# KellyConnections.net
KiCad netlist of a schematic drawn in EAGLE
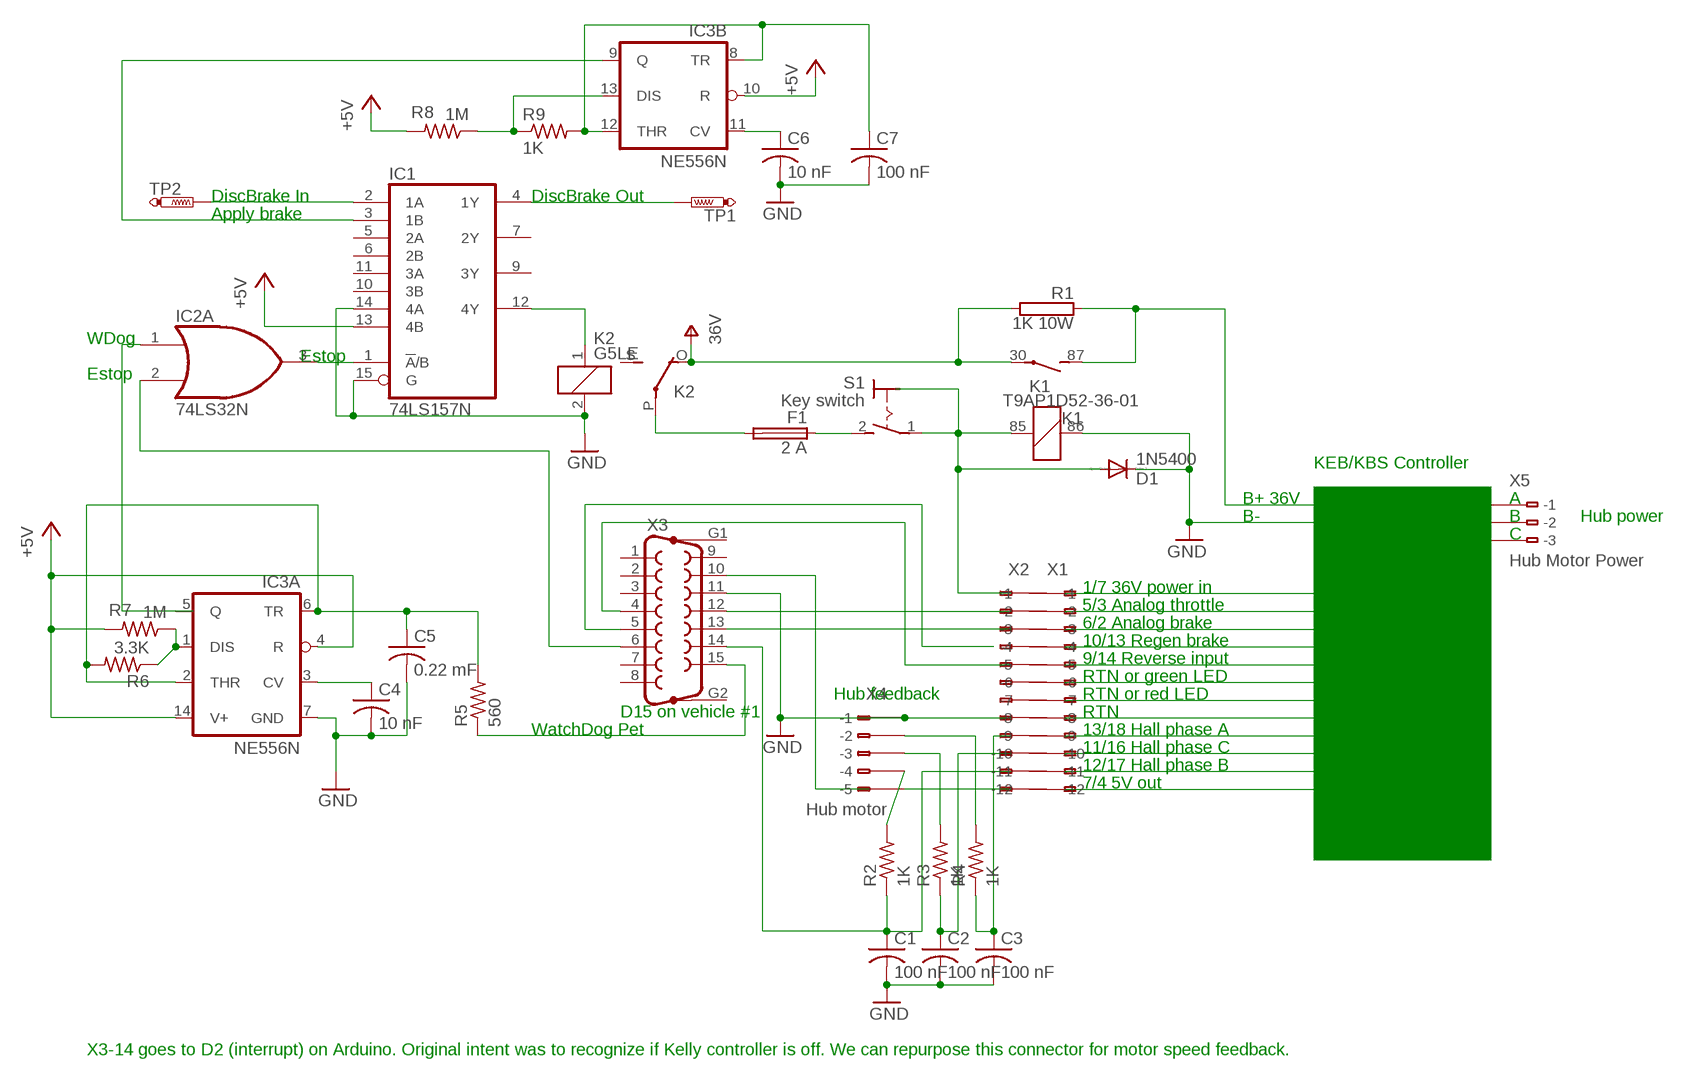
[diagram p0: schematic, sheet 1]

(export (version "E")
  (design (tool "Eeschema 10.0.6"))
  (components
    (comp (ref "C1")
      (value "100 nF")
      (footprint "eagle-import:C025-025X050")
      (libsource (lib "eagle-import") (part "C-US025-025X050"))
    )
    (comp (ref "C2")
      (value "100 nF")
      (footprint "eagle-import:C025-025X050")
      (libsource (lib "eagle-import") (part "C-US025-025X050"))
    )
    (comp (ref "C3")
      (value "100 nF")
      (footprint "eagle-import:C025-025X050")
      (libsource (lib "eagle-import") (part "C-US025-025X050"))
    )
    (comp (ref "C4")
      (value "10 nF")
      (footprint "eagle-import:C025-025X050")
      (libsource (lib "eagle-import") (part "C-US025-025X050"))
    )
    (comp (ref "C5")
      (value "0.22 mF")
      (footprint "eagle-import:C025-025X050")
      (libsource (lib "eagle-import") (part "C-US025-025X050"))
    )
    (comp (ref "C6")
      (value "10 nF")
      (footprint "eagle-import:C025-025X050")
      (libsource (lib "eagle-import") (part "C-US025-025X050"))
    )
    (comp (ref "C7")
      (value "100 nF")
      (footprint "eagle-import:C025-025X050")
      (libsource (lib "eagle-import") (part "C-US025-025X050"))
    )
    (comp (ref "D1")
      (value "1N5400")
      (footprint "eagle-import:DO201-15")
      (libsource (lib "eagle-import") (part "1N5400"))
    )
    (comp (ref "F1")
      (value "2 A")
      (footprint "eagle-import:TE5")
      (libsource (lib "eagle-import") (part "TE5"))
    )
    (comp (ref "IC1")
      (value "74LS157N")
      (footprint "eagle-import:DIL16")
      (libsource (lib "eagle-import") (part "74157NLS"))
    )
    (comp (ref "IC2")
      (value "74LS32N")
      (footprint "eagle-import:DIL14")
      (libsource (lib "eagle-import") (part "7432NLS"))
    )
    (comp (ref "IC3")
      (value "NE556N")
      (footprint "eagle-import:DIL14")
      (libsource (lib "eagle-import") (part "556NNE"))
    )
    (comp (ref "K1")
      (value "T9AP1D52-36-01")
      (footprint "eagle-import:CB1")
      (fields (field (name "MF") "AROMAT/ MATSUSHITA") (field (name "MPN") "CB1A-P-12V"))
      (libsource (lib "eagle-import") (part "CB1A-P-12V"))
    )
    (comp (ref "K2")
      (value "G5LE")
      (footprint "eagle-import:G5LE")
      (libsource (lib "eagle-import") (part "G5LE"))
    )
    (comp (ref "R1")
      (value "1K 10W")
      (footprint "eagle-import:AC07")
      (libsource (lib "eagle-import") (part "RAC07"))
    )
    (comp (ref "R2")
      (value "1K")
      (footprint "eagle-import:0207_15")
      (libsource (lib "eagle-import") (part "R-US_0207/15"))
    )
    (comp (ref "R3")
      (value "1K")
      (footprint "eagle-import:0207_15")
      (libsource (lib "eagle-import") (part "R-US_0207/15"))
    )
    (comp (ref "R4")
      (value "1K")
      (footprint "eagle-import:0207_15")
      (libsource (lib "eagle-import") (part "R-US_0207/15"))
    )
    (comp (ref "R5")
      (value "560")
      (footprint "eagle-import:0207_15")
      (libsource (lib "eagle-import") (part "R-US_0207/15"))
    )
    (comp (ref "R6")
      (value "3.3K")
      (footprint "eagle-import:0207_15")
      (libsource (lib "eagle-import") (part "R-US_0207/15"))
    )
    (comp (ref "R7")
      (value "1M")
      (footprint "eagle-import:0207_15")
      (libsource (lib "eagle-import") (part "R-US_0207/15"))
    )
    (comp (ref "R8")
      (value "1M")
      (footprint "eagle-import:0207_15")
      (libsource (lib "eagle-import") (part "R-US_0207/15"))
    )
    (comp (ref "R9")
      (value "1K")
      (footprint "eagle-import:0207_15")
      (libsource (lib "eagle-import") (part "R-US_0207/15"))
    )
    (comp (ref "S1")
      (value "Key switch")
      (footprint "eagle-import:MS243")
      (libsource (lib "eagle-import") (part "MS243"))
    )
    (comp (ref "TP1")
      (value "PTR1B1,27")
      (footprint "eagle-import:B1,27")
      (libsource (lib "eagle-import") (part "PTR1B1,27"))
    )
    (comp (ref "TP2")
      (value "PTR1B1,27")
      (footprint "eagle-import:B1,27")
      (libsource (lib "eagle-import") (part "PTR1B1,27"))
    )
    (comp (ref "X1")
      (value "233-112")
      (footprint "eagle-import:233-112")
      (libsource (lib "eagle-import") (part "233-112"))
    )
    (comp (ref "X2")
      (value "233-112")
      (footprint "eagle-import:233-112")
      (libsource (lib "eagle-import") (part "233-112"))
    )
    (comp (ref "X3")
      (value "F15HP")
      (footprint "eagle-import:F15HP")
      (libsource (lib "eagle-import") (part "F15HP"))
    )
    (comp (ref "X4")
      (value "Hub motor")
      (footprint "eagle-import:233-105")
      (fields (field (name "MPN") "233-105"))
      (libsource (lib "eagle-import") (part "233-105"))
    )
    (comp (ref "X5")
      (value "Hub Motor Power")
      (footprint "eagle-import:233-103")
      (fields (field (name "MPN") "233-103"))
      (libsource (lib "eagle-import") (part "233-103"))
    )
  )
  (nets
    (net (code "1") (name "+5V") (class "Default")
      (node (ref "IC1") (pin "13") (pinfunction "4B_13") (pintype "input"))
      (node (ref "IC3") (pin "10") (pinfunction "R_10") (pintype "input"))
      (node (ref "IC3") (pin "14") (pinfunction "V+_14") (pintype "power_in"))
      (node (ref "IC3") (pin "4") (pinfunction "R_4") (pintype "input"))
      (node (ref "R7") (pin "2") (pinfunction "2_2") (pintype "passive"))
      (node (ref "R8") (pin "2") (pinfunction "2_2") (pintype "passive"))
    )
    (net (code "2") (name "36V") (class "Default")
      (node (ref "K1") (pin "30") (pinfunction "P_30") (pintype "passive"))
      (node (ref "K2") (pin "O") (pinfunction "O_O") (pintype "passive"))
      (node (ref "R1") (pin "2") (pinfunction "2_2") (pintype "passive"))
    )
    (net (code "3") (name "GND") (class "Default")
      (node (ref "C1") (pin "2") (pinfunction "2_2") (pintype "passive"))
      (node (ref "C2") (pin "2") (pinfunction "2_2") (pintype "passive"))
      (node (ref "C3") (pin "2") (pinfunction "2_2") (pintype "passive"))
      (node (ref "C4") (pin "2") (pinfunction "2_2") (pintype "passive"))
      (node (ref "C5") (pin "2") (pinfunction "2_2") (pintype "passive"))
      (node (ref "C6") (pin "2") (pinfunction "2_2") (pintype "passive"))
      (node (ref "C7") (pin "2") (pinfunction "2_2") (pintype "passive"))
      (node (ref "D1") (pin "C") (pinfunction "C_C") (pintype "passive"))
      (node (ref "IC1") (pin "14") (pinfunction "4A_14") (pintype "input"))
      (node (ref "IC1") (pin "15") (pinfunction "G_15") (pintype "input"))
      (node (ref "IC3") (pin "7") (pinfunction "GND_7") (pintype "power_in"))
      (node (ref "K1") (pin "86") (pinfunction "1_86") (pintype "passive"))
      (node (ref "K2") (pin "2") (pinfunction "2_2") (pintype "passive"))
      (node (ref "X3") (pin "11") (pinfunction "11_11") (pintype "passive"))
      (node (ref "X4") (pin "A1") (pinfunction "-1_A1") (pintype "passive"))
      (node (ref "X4") (pin "B1") (pinfunction "B-1_B1") (pintype "passive"))
    )
    (net (code "4") (name "Net-(C1-Pad1)") (class "Default")
      (node (ref "C1") (pin "1") (pinfunction "1_1") (pintype "passive"))
      (node (ref "R2") (pin "1") (pinfunction "1_1") (pintype "passive"))
      (node (ref "X3") (pin "14") (pinfunction "14_14") (pintype "passive"))
    )
    (net (code "5") (name "Net-(C2-Pad1)") (class "Default")
      (node (ref "C2") (pin "1") (pinfunction "1_1") (pintype "passive"))
      (node (ref "R3") (pin "1") (pinfunction "1_1") (pintype "passive"))
    )
    (net (code "6") (name "Net-(C3-Pad1)") (class "Default")
      (node (ref "C3") (pin "1") (pinfunction "1_1") (pintype "passive"))
      (node (ref "R4") (pin "1") (pinfunction "1_1") (pintype "passive"))
    )
    (net (code "7") (name "Net-(F1-Pad2)") (class "Default")
      (node (ref "F1") (pin "2") (pinfunction "2_2") (pintype "passive"))
      (node (ref "K2") (pin "P") (pinfunction "P_P") (pintype "passive"))
    )
    (net (code "8") (name "Net-(IC1A-1A)") (class "Default")
      (node (ref "IC1") (pin "2") (pinfunction "1A_2") (pintype "input"))
      (node (ref "TP2") (pin "TP") (pinfunction "TP_TP") (pintype "input"))
    )
    (net (code "9") (name "Net-(IC1A-1B)") (class "Default")
      (node (ref "IC1") (pin "3") (pinfunction "1B_3") (pintype "input"))
      (node (ref "IC3") (pin "9") (pinfunction "Q_9") (pintype "output"))
    )
    (net (code "10") (name "Net-(IC1A-1Y)") (class "Default")
      (node (ref "IC1") (pin "4") (pinfunction "1Y_4") (pintype "output"))
      (node (ref "TP1") (pin "TP") (pinfunction "TP_TP") (pintype "input"))
    )
    (net (code "11") (name "Net-(IC1A-4Y)") (class "Default")
      (node (ref "IC1") (pin "12") (pinfunction "4Y_12") (pintype "output"))
      (node (ref "K2") (pin "1") (pinfunction "1_1") (pintype "passive"))
    )
    (net (code "12") (name "Net-(IC1A-~{A}{slash}B)") (class "Default")
      (node (ref "IC1") (pin "1") (pinfunction "~{A}/B_1") (pintype "input"))
      (node (ref "IC2") (pin "3") (pinfunction "O_3") (pintype "output"))
    )
    (net (code "13") (name "Net-(IC2A-I1)") (class "Default")
      (node (ref "IC2") (pin "2") (pinfunction "I1_2") (pintype "input"))
      (node (ref "X3") (pin "6") (pinfunction "6_6") (pintype "passive"))
    )
    (net (code "14") (name "Net-(IC3A-CV)") (class "Default")
      (node (ref "C4") (pin "1") (pinfunction "1_1") (pintype "passive"))
      (node (ref "IC3") (pin "3") (pinfunction "CV_3") (pintype "input"))
    )
    (net (code "15") (name "Net-(IC3A-DIS)") (class "Default")
      (node (ref "IC3") (pin "1") (pinfunction "DIS_1") (pintype "input"))
      (node (ref "R6") (pin "1") (pinfunction "1_1") (pintype "passive"))
      (node (ref "R7") (pin "1") (pinfunction "1_1") (pintype "passive"))
    )
    (net (code "16") (name "Net-(IC3A-THR)") (class "Default")
      (node (ref "C5") (pin "1") (pinfunction "1_1") (pintype "passive"))
      (node (ref "IC3") (pin "2") (pinfunction "THR_2") (pintype "input"))
      (node (ref "IC3") (pin "6") (pinfunction "TR_6") (pintype "input"))
      (node (ref "R5") (pin "2") (pinfunction "2_2") (pintype "passive"))
      (node (ref "R6") (pin "2") (pinfunction "2_2") (pintype "passive"))
    )
    (net (code "17") (name "Net-(IC3B-CV)") (class "Default")
      (node (ref "C6") (pin "1") (pinfunction "1_1") (pintype "passive"))
      (node (ref "IC3") (pin "11") (pinfunction "CV_11") (pintype "input"))
    )
    (net (code "18") (name "Net-(IC3B-DIS)") (class "Default")
      (node (ref "IC3") (pin "13") (pinfunction "DIS_13") (pintype "input"))
      (node (ref "R8") (pin "1") (pinfunction "1_1") (pintype "passive"))
      (node (ref "R9") (pin "1") (pinfunction "1_1") (pintype "passive"))
    )
    (net (code "19") (name "Net-(IC3B-THR)") (class "Default")
      (node (ref "C7") (pin "1") (pinfunction "1_1") (pintype "passive"))
      (node (ref "IC3") (pin "12") (pinfunction "THR_12") (pintype "input"))
      (node (ref "IC3") (pin "8") (pinfunction "TR_8") (pintype "input"))
      (node (ref "R9") (pin "2") (pinfunction "2_2") (pintype "passive"))
    )
    (net (code "20") (name "Net-(K1A-2)") (class "Default")
      (node (ref "D1") (pin "A") (pinfunction "A_A") (pintype "passive"))
      (node (ref "K1") (pin "85") (pinfunction "2_85") (pintype "passive"))
      (node (ref "S1") (pin "1") (pinfunction "P_1") (pintype "passive"))
    )
    (net (code "21") (name "Net-(K1B-S)") (class "Default")
      (node (ref "K1") (pin "87") (pinfunction "S_87") (pintype "passive"))
      (node (ref "R1") (pin "1") (pinfunction "1_1") (pintype "passive"))
    )
    (net (code "22") (name "Net-(R5-Pad1)") (class "Default")
      (node (ref "R5") (pin "1") (pinfunction "1_1") (pintype "passive"))
      (node (ref "X3") (pin "15") (pinfunction "15_15") (pintype "passive"))
    )
    (net (code "23") (name "Net-(S1-S)") (class "Default")
      (node (ref "F1") (pin "1") (pinfunction "1_1") (pintype "passive"))
      (node (ref "S1") (pin "2") (pinfunction "S_2") (pintype "passive"))
    )
    (net (code "24") (name "Net-(X1--1)") (class "Default")
      (node (ref "X1") (pin "A1") (pinfunction "-1_A1") (pintype "passive"))
      (node (ref "X2") (pin "B1") (pinfunction "B-1_B1") (pintype "passive"))
    )
    (net (code "25") (name "Net-(X1--2)") (class "Default")
      (node (ref "X1") (pin "A2") (pinfunction "-2_A2") (pintype "passive"))
      (node (ref "X2") (pin "B2") (pinfunction "B-2_B2") (pintype "passive"))
    )
    (net (code "26") (name "Net-(X1--3)") (class "Default")
      (node (ref "X1") (pin "A3") (pinfunction "-3_A3") (pintype "passive"))
      (node (ref "X2") (pin "B3") (pinfunction "B-3_B3") (pintype "passive"))
    )
    (net (code "27") (name "Net-(X1--4)") (class "Default")
      (node (ref "X1") (pin "A4") (pinfunction "-4_A4") (pintype "passive"))
      (node (ref "X2") (pin "B4") (pinfunction "B-4_B4") (pintype "passive"))
    )
    (net (code "28") (name "Net-(X1--5)") (class "Default")
      (node (ref "X1") (pin "A5") (pinfunction "-5_A5") (pintype "passive"))
      (node (ref "X2") (pin "B5") (pinfunction "B-5_B5") (pintype "passive"))
    )
    (net (code "29") (name "Net-(X1--6)") (class "Default")
      (node (ref "X1") (pin "A6") (pinfunction "-6_A6") (pintype "passive"))
      (node (ref "X2") (pin "B6") (pinfunction "B-6_B6") (pintype "passive"))
    )
    (net (code "30") (name "Net-(X1--7)") (class "Default")
      (node (ref "X1") (pin "A7") (pinfunction "-7_A7") (pintype "passive"))
      (node (ref "X2") (pin "B7") (pinfunction "B-7_B7") (pintype "passive"))
    )
    (net (code "31") (name "Net-(X1--8)") (class "Default")
      (node (ref "X1") (pin "A8") (pinfunction "-8_A8") (pintype "passive"))
      (node (ref "X2") (pin "B8") (pinfunction "B-8_B8") (pintype "passive"))
    )
    (net (code "32") (name "Net-(X1--9)") (class "Default")
      (node (ref "X1") (pin "A9") (pinfunction "-9_A9") (pintype "passive"))
      (node (ref "X2") (pin "B9") (pinfunction "B-9_B9") (pintype "passive"))
    )
    (net (code "33") (name "Net-(X1--10)") (class "Default")
      (node (ref "X1") (pin "A10") (pinfunction "-10_A10") (pintype "passive"))
      (node (ref "X2") (pin "B10") (pinfunction "B-10_B10") (pintype "passive"))
    )
    (net (code "34") (name "Net-(X1--11)") (class "Default")
      (node (ref "X1") (pin "A11") (pinfunction "-11_A11") (pintype "passive"))
      (node (ref "X2") (pin "B11") (pinfunction "B-11_B11") (pintype "passive"))
    )
    (net (code "35") (name "Net-(X1--12)") (class "Default")
      (node (ref "X1") (pin "A12") (pinfunction "-12_A12") (pintype "passive"))
      (node (ref "X2") (pin "B12") (pinfunction "B-12_B12") (pintype "passive"))
    )
    (net (code "36") (name "Net-(X1-B-1)") (class "Default")
      (node (ref "X1") (pin "B1") (pinfunction "B-1_B1") (pintype "passive"))
      (node (ref "X2") (pin "A1") (pinfunction "-1_A1") (pintype "passive"))
    )
    (net (code "37") (name "Net-(X1-B-2)") (class "Default")
      (node (ref "X1") (pin "B2") (pinfunction "B-2_B2") (pintype "passive"))
      (node (ref "X2") (pin "A2") (pinfunction "-2_A2") (pintype "passive"))
    )
    (net (code "38") (name "Net-(X1-B-3)") (class "Default")
      (node (ref "X1") (pin "B3") (pinfunction "B-3_B3") (pintype "passive"))
      (node (ref "X2") (pin "A3") (pinfunction "-3_A3") (pintype "passive"))
    )
    (net (code "39") (name "Net-(X1-B-4)") (class "Default")
      (node (ref "X1") (pin "B4") (pinfunction "B-4_B4") (pintype "passive"))
      (node (ref "X2") (pin "A4") (pinfunction "-4_A4") (pintype "passive"))
    )
    (net (code "40") (name "Net-(X1-B-5)") (class "Default")
      (node (ref "X1") (pin "B5") (pinfunction "B-5_B5") (pintype "passive"))
      (node (ref "X2") (pin "A5") (pinfunction "-5_A5") (pintype "passive"))
    )
    (net (code "41") (name "Net-(X1-B-6)") (class "Default")
      (node (ref "X1") (pin "B6") (pinfunction "B-6_B6") (pintype "passive"))
      (node (ref "X2") (pin "A6") (pinfunction "-6_A6") (pintype "passive"))
    )
    (net (code "42") (name "Net-(X1-B-7)") (class "Default")
      (node (ref "X1") (pin "B7") (pinfunction "B-7_B7") (pintype "passive"))
      (node (ref "X2") (pin "A7") (pinfunction "-7_A7") (pintype "passive"))
    )
    (net (code "43") (name "Net-(X1-B-8)") (class "Default")
      (node (ref "X1") (pin "B8") (pinfunction "B-8_B8") (pintype "passive"))
      (node (ref "X2") (pin "A8") (pinfunction "-8_A8") (pintype "passive"))
    )
    (net (code "44") (name "Net-(X1-B-9)") (class "Default")
      (node (ref "X1") (pin "B9") (pinfunction "B-9_B9") (pintype "passive"))
      (node (ref "X2") (pin "A9") (pinfunction "-9_A9") (pintype "passive"))
    )
    (net (code "45") (name "Net-(X1-B-10)") (class "Default")
      (node (ref "X1") (pin "B10") (pinfunction "B-10_B10") (pintype "passive"))
      (node (ref "X2") (pin "A10") (pinfunction "-10_A10") (pintype "passive"))
    )
    (net (code "46") (name "Net-(X1-B-11)") (class "Default")
      (node (ref "X1") (pin "B11") (pinfunction "B-11_B11") (pintype "passive"))
      (node (ref "X2") (pin "A11") (pinfunction "-11_A11") (pintype "passive"))
    )
    (net (code "47") (name "Net-(X1-B-12)") (class "Default")
      (node (ref "X1") (pin "B12") (pinfunction "B-12_B12") (pintype "passive"))
      (node (ref "X2") (pin "A12") (pinfunction "-12_A12") (pintype "passive"))
    )
    (net (code "48") (name "Net-(X4-B-2)") (class "Default")
      (node (ref "R4") (pin "2") (pinfunction "2_2") (pintype "passive"))
      (node (ref "X4") (pin "B2") (pinfunction "B-2_B2") (pintype "passive"))
    )
    (net (code "49") (name "Net-(X4-B-3)") (class "Default")
      (node (ref "R3") (pin "2") (pinfunction "2_2") (pintype "passive"))
      (node (ref "X4") (pin "B3") (pinfunction "B-3_B3") (pintype "passive"))
    )
    (net (code "50") (name "Net-(X4-B-4)") (class "Default")
      (node (ref "R2") (pin "2") (pinfunction "2_2") (pintype "passive"))
      (node (ref "X4") (pin "B4") (pinfunction "B-4_B4") (pintype "passive"))
    )
    (net (code "51") (name "unconnected-(IC1A-2A-Pad5)") (class "Default")
      (node (ref "IC1") (pin "5") (pinfunction "2A_5") (pintype "input"))
    )
    (net (code "52") (name "unconnected-(IC1A-2B-Pad6)") (class "Default")
      (node (ref "IC1") (pin "6") (pinfunction "2B_6") (pintype "input"))
    )
    (net (code "53") (name "unconnected-(IC1A-2Y-Pad7)") (class "Default")
      (node (ref "IC1") (pin "7") (pinfunction "2Y_7") (pintype "output"))
    )
    (net (code "54") (name "unconnected-(IC1A-3A-Pad11)") (class "Default")
      (node (ref "IC1") (pin "11") (pinfunction "3A_11") (pintype "input"))
    )
    (net (code "55") (name "unconnected-(IC1A-3B-Pad10)") (class "Default")
      (node (ref "IC1") (pin "10") (pinfunction "3B_10") (pintype "input"))
    )
    (net (code "56") (name "unconnected-(IC1A-3Y-Pad9)") (class "Default")
      (node (ref "IC1") (pin "9") (pinfunction "3Y_9") (pintype "output"))
    )
    (net (code "57") (name "unconnected-(IC2A-I0-Pad1)") (class "Default")
      (node (ref "IC2") (pin "1") (pinfunction "I0_1") (pintype "input"))
    )
    (net (code "58") (name "unconnected-(IC3A-Q-Pad5)") (class "Default")
      (node (ref "IC3") (pin "5") (pinfunction "Q_5") (pintype "output"))
    )
    (net (code "59") (name "unconnected-(K2-PadS)") (class "Default")
      (node (ref "K2") (pin "S") (pinfunction "S_S") (pintype "passive"))
    )
    (net (code "60") (name "unconnected-(X3-Pad1)") (class "Default")
      (node (ref "X3") (pin "1") (pinfunction "1_1") (pintype "passive"))
    )
    (net (code "61") (name "unconnected-(X3-Pad2)") (class "Default")
      (node (ref "X3") (pin "2") (pinfunction "2_2") (pintype "passive"))
    )
    (net (code "62") (name "unconnected-(X3-Pad3)") (class "Default")
      (node (ref "X3") (pin "3") (pinfunction "3_3") (pintype "passive"))
    )
    (net (code "63") (name "unconnected-(X3-Pad4)") (class "Default")
      (node (ref "X3") (pin "4") (pinfunction "4_4") (pintype "passive"))
    )
    (net (code "64") (name "unconnected-(X3-Pad5)") (class "Default")
      (node (ref "X3") (pin "5") (pinfunction "5_5") (pintype "passive"))
    )
    (net (code "65") (name "unconnected-(X3-Pad7)") (class "Default")
      (node (ref "X3") (pin "7") (pinfunction "7_7") (pintype "passive"))
    )
    (net (code "66") (name "unconnected-(X3-Pad8)") (class "Default")
      (node (ref "X3") (pin "8") (pinfunction "8_8") (pintype "passive"))
    )
    (net (code "67") (name "unconnected-(X3-Pad9)") (class "Default")
      (node (ref "X3") (pin "9") (pinfunction "9_9") (pintype "passive"))
    )
    (net (code "68") (name "unconnected-(X3-Pad10)") (class "Default")
      (node (ref "X3") (pin "10") (pinfunction "10_10") (pintype "passive"))
    )
    (net (code "69") (name "unconnected-(X3-Pad12)") (class "Default")
      (node (ref "X3") (pin "12") (pinfunction "12_12") (pintype "passive"))
    )
    (net (code "70") (name "unconnected-(X3-Pad13)") (class "Default")
      (node (ref "X3") (pin "13") (pinfunction "13_13") (pintype "passive"))
    )
    (net (code "71") (name "unconnected-(X3-PadG1)") (class "Default")
      (node (ref "X3") (pin "G1") (pinfunction "G1_G1") (pintype "passive"))
    )
    (net (code "72") (name "unconnected-(X3-PadG2)") (class "Default")
      (node (ref "X3") (pin "G2") (pinfunction "G2_G2") (pintype "passive"))
    )
    (net (code "73") (name "unconnected-(X4--2-PadA2)") (class "Default")
      (node (ref "X4") (pin "A2") (pinfunction "-2_A2") (pintype "passive"))
    )
    (net (code "74") (name "unconnected-(X4--3-PadA3)") (class "Default")
      (node (ref "X4") (pin "A3") (pinfunction "-3_A3") (pintype "passive"))
    )
    (net (code "75") (name "unconnected-(X4--4-PadA4)") (class "Default")
      (node (ref "X4") (pin "A4") (pinfunction "-4_A4") (pintype "passive"))
    )
    (net (code "76") (name "unconnected-(X4--5-PadA5)") (class "Default")
      (node (ref "X4") (pin "A5") (pinfunction "-5_A5") (pintype "passive"))
    )
    (net (code "77") (name "unconnected-(X4-B-5-PadB5)") (class "Default")
      (node (ref "X4") (pin "B5") (pinfunction "B-5_B5") (pintype "passive"))
    )
    (net (code "78") (name "unconnected-(X5--1-PadA1)") (class "Default")
      (node (ref "X5") (pin "A1") (pinfunction "-1_A1") (pintype "passive"))
    )
    (net (code "79") (name "unconnected-(X5--2-PadA2)") (class "Default")
      (node (ref "X5") (pin "A2") (pinfunction "-2_A2") (pintype "passive"))
    )
    (net (code "80") (name "unconnected-(X5--3-PadA3)") (class "Default")
      (node (ref "X5") (pin "A3") (pinfunction "-3_A3") (pintype "passive"))
    )
    (net (code "81") (name "unconnected-(X5-B-1-PadB1)") (class "Default")
      (node (ref "X5") (pin "B1") (pinfunction "B-1_B1") (pintype "passive"))
    )
    (net (code "82") (name "unconnected-(X5-B-2-PadB2)") (class "Default")
      (node (ref "X5") (pin "B2") (pinfunction "B-2_B2") (pintype "passive"))
    )
    (net (code "83") (name "unconnected-(X5-B-3-PadB3)") (class "Default")
      (node (ref "X5") (pin "B3") (pinfunction "B-3_B3") (pintype "passive"))
    )
  )
)
